# sensor_board.net
KiCad netlist of a schematic drawn in EAGLE
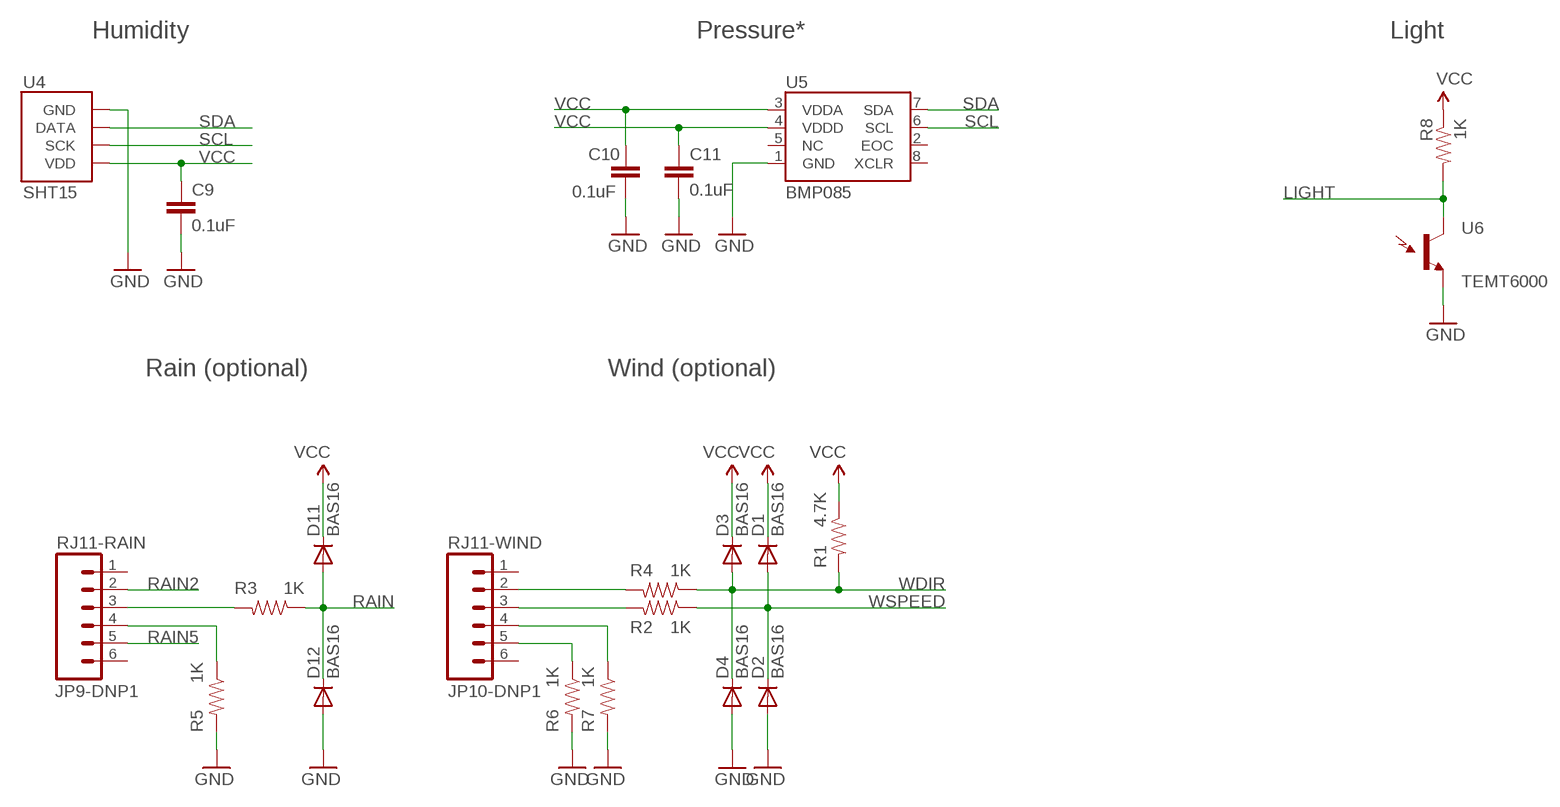
[diagram p0: schematic, sheet 1]

(export (version "E")
  (design (tool "Eeschema 10.0.6"))
  (components
    (comp (ref "C9")
      (value "0.1uF")
      (footprint "eagle-import:0402-CAP")
      (libsource (lib "eagle-import") (part "CAP0402-CAP"))
    )
    (comp (ref "C10")
      (value "0.1uF")
      (footprint "eagle-import:0402-CAP")
      (libsource (lib "eagle-import") (part "CAP0402-CAP"))
    )
    (comp (ref "C11")
      (value "0.1uF")
      (footprint "eagle-import:0402-CAP")
      (libsource (lib "eagle-import") (part "CAP0402-CAP"))
    )
    (comp (ref "D1")
      (value "BAS16")
      (footprint "eagle-import:SOD-323")
      (libsource (lib "eagle-import") (part "DIODESOD"))
    )
    (comp (ref "D2")
      (value "BAS16")
      (footprint "eagle-import:SOD-323")
      (libsource (lib "eagle-import") (part "DIODESOD"))
    )
    (comp (ref "D3")
      (value "BAS16")
      (footprint "eagle-import:SOD-323")
      (libsource (lib "eagle-import") (part "DIODESOD"))
    )
    (comp (ref "D4")
      (value "BAS16")
      (footprint "eagle-import:SOD-323")
      (libsource (lib "eagle-import") (part "DIODESOD"))
    )
    (comp (ref "D11")
      (value "BAS16")
      (footprint "eagle-import:SOD-323")
      (libsource (lib "eagle-import") (part "DIODESOD"))
    )
    (comp (ref "D12")
      (value "BAS16")
      (footprint "eagle-import:SOD-323")
      (libsource (lib "eagle-import") (part "DIODESOD"))
    )
    (comp (ref "JP9-DNP1")
      (value "RJ11-RAIN")
      (footprint "eagle-import:RJ11-6")
      (libsource (lib "eagle-import") (part "RJ11-6PTH"))
    )
    (comp (ref "JP10-DNP1")
      (value "RJ11-WIND")
      (footprint "eagle-import:RJ11-6")
      (libsource (lib "eagle-import") (part "RJ11-6PTH"))
    )
    (comp (ref "R1")
      (value "4.7K")
      (footprint "eagle-import:0402-RES")
      (libsource (lib "eagle-import") (part "RESISTOR0402-RES"))
    )
    (comp (ref "R2")
      (value "1K")
      (footprint "eagle-import:0402-RES")
      (libsource (lib "eagle-import") (part "RESISTOR0402-RES"))
    )
    (comp (ref "R3")
      (value "1K")
      (footprint "eagle-import:0402-RES")
      (libsource (lib "eagle-import") (part "RESISTOR0402-RES"))
    )
    (comp (ref "R4")
      (value "1K")
      (footprint "eagle-import:0402-RES")
      (libsource (lib "eagle-import") (part "RESISTOR0402-RES"))
    )
    (comp (ref "R5")
      (value "1K")
      (footprint "eagle-import:0402-RES")
      (libsource (lib "eagle-import") (part "RESISTOR0402-RES"))
    )
    (comp (ref "R6")
      (value "1K")
      (footprint "eagle-import:0402-RES")
      (libsource (lib "eagle-import") (part "RESISTOR0402-RES"))
    )
    (comp (ref "R7")
      (value "1K")
      (footprint "eagle-import:0402-RES")
      (libsource (lib "eagle-import") (part "RESISTOR0402-RES"))
    )
    (comp (ref "R8")
      (value "1K")
      (footprint "eagle-import:0402-RES")
      (libsource (lib "eagle-import") (part "RESISTOR0402-RES"))
    )
    (comp (ref "U4")
      (value "SHT15")
      (footprint "eagle-import:SHT1X")
      (libsource (lib "eagle-import") (part "SHT1XSMD"))
    )
    (comp (ref "U5")
      (value "BMP085")
      (footprint "eagle-import:BMP085")
      (libsource (lib "eagle-import") (part "BMP085"))
    )
    (comp (ref "U6")
      (value "TEMT6000")
      (footprint "eagle-import:TEMT6000-SEN")
      (libsource (lib "eagle-import") (part "TEMT6000"))
    )
  )
  (nets
    (net (code "1") (name "/LIGHT") (class "Default")
      (node (ref "R8") (pin "2") (pinfunction "2_2") (pintype "passive"))
      (node (ref "U6") (pin "COLLECTOR") (pinfunction "C1_COLLECTOR") (pintype "passive"))
    )
    (net (code "2") (name "/RAIN") (class "Default")
      (node (ref "D11") (pin "2") (pinfunction "A_2") (pintype "passive"))
      (node (ref "D12") (pin "1") (pinfunction "C_1") (pintype "passive"))
      (node (ref "R3") (pin "1") (pinfunction "1_1") (pintype "passive"))
    )
    (net (code "3") (name "/RAIN2") (class "Default")
      (node (ref "JP9-DNP1") (pin "2") (pinfunction "2_2") (pintype "passive"))
    )
    (net (code "4") (name "/RAIN5") (class "Default")
      (node (ref "JP9-DNP1") (pin "5") (pinfunction "5_5") (pintype "passive"))
    )
    (net (code "5") (name "/SCL") (class "Default")
      (node (ref "U4") (pin "3") (pinfunction "SCK_3") (pintype "input"))
      (node (ref "U5") (pin "6") (pinfunction "SCL_6") (pintype "input"))
    )
    (net (code "6") (name "/SDA") (class "Default")
      (node (ref "U4") (pin "2") (pinfunction "DATA_2") (pintype "bidirectional"))
      (node (ref "U5") (pin "7") (pinfunction "SDA_7") (pintype "bidirectional"))
    )
    (net (code "7") (name "/WDIR") (class "Default")
      (node (ref "D3") (pin "2") (pinfunction "A_2") (pintype "passive"))
      (node (ref "D4") (pin "1") (pinfunction "C_1") (pintype "passive"))
      (node (ref "R1") (pin "2") (pinfunction "2_2") (pintype "passive"))
      (node (ref "R4") (pin "1") (pinfunction "1_1") (pintype "passive"))
    )
    (net (code "8") (name "/WSPEED") (class "Default")
      (node (ref "D1") (pin "2") (pinfunction "A_2") (pintype "passive"))
      (node (ref "D2") (pin "1") (pinfunction "C_1") (pintype "passive"))
      (node (ref "R2") (pin "1") (pinfunction "1_1") (pintype "passive"))
    )
    (net (code "9") (name "GND") (class "Default")
      (node (ref "C10") (pin "1") (pinfunction "1_1") (pintype "passive"))
      (node (ref "C11") (pin "2") (pinfunction "2_2") (pintype "passive"))
      (node (ref "C9") (pin "2") (pinfunction "2_2") (pintype "passive"))
      (node (ref "D12") (pin "2") (pinfunction "A_2") (pintype "passive"))
      (node (ref "D2") (pin "2") (pinfunction "A_2") (pintype "passive"))
      (node (ref "D4") (pin "2") (pinfunction "A_2") (pintype "passive"))
      (node (ref "R5") (pin "2") (pinfunction "2_2") (pintype "passive"))
      (node (ref "R6") (pin "2") (pinfunction "2_2") (pintype "passive"))
      (node (ref "R7") (pin "2") (pinfunction "2_2") (pintype "passive"))
      (node (ref "U4") (pin "1") (pinfunction "GND_1") (pintype "power_in"))
      (node (ref "U5") (pin "1") (pinfunction "GND_1") (pintype "power_in"))
      (node (ref "U6") (pin "EMITTER") (pinfunction "E1_EMITTER") (pintype "passive"))
    )
    (net (code "10") (name "Net-(JP9-DNP1-Pad3)") (class "Default")
      (node (ref "JP9-DNP1") (pin "3") (pinfunction "3_3") (pintype "passive"))
      (node (ref "R3") (pin "2") (pinfunction "2_2") (pintype "passive"))
    )
    (net (code "11") (name "Net-(JP9-DNP1-Pad4)") (class "Default")
      (node (ref "JP9-DNP1") (pin "4") (pinfunction "4_4") (pintype "passive"))
      (node (ref "R5") (pin "1") (pinfunction "1_1") (pintype "passive"))
    )
    (net (code "12") (name "Net-(JP10-DNP1-Pad2)") (class "Default")
      (node (ref "JP10-DNP1") (pin "2") (pinfunction "2_2") (pintype "passive"))
      (node (ref "R4") (pin "2") (pinfunction "2_2") (pintype "passive"))
    )
    (net (code "13") (name "Net-(JP10-DNP1-Pad3)") (class "Default")
      (node (ref "JP10-DNP1") (pin "3") (pinfunction "3_3") (pintype "passive"))
      (node (ref "R2") (pin "2") (pinfunction "2_2") (pintype "passive"))
    )
    (net (code "14") (name "Net-(JP10-DNP1-Pad4)") (class "Default")
      (node (ref "JP10-DNP1") (pin "4") (pinfunction "4_4") (pintype "passive"))
      (node (ref "R7") (pin "1") (pinfunction "1_1") (pintype "passive"))
    )
    (net (code "15") (name "Net-(JP10-DNP1-Pad5)") (class "Default")
      (node (ref "JP10-DNP1") (pin "5") (pinfunction "5_5") (pintype "passive"))
      (node (ref "R6") (pin "1") (pinfunction "1_1") (pintype "passive"))
    )
    (net (code "16") (name "VCC") (class "Default")
      (node (ref "C10") (pin "2") (pinfunction "2_2") (pintype "passive"))
      (node (ref "C11") (pin "1") (pinfunction "1_1") (pintype "passive"))
      (node (ref "C9") (pin "1") (pinfunction "1_1") (pintype "passive"))
      (node (ref "D1") (pin "1") (pinfunction "C_1") (pintype "passive"))
      (node (ref "D11") (pin "1") (pinfunction "C_1") (pintype "passive"))
      (node (ref "D3") (pin "1") (pinfunction "C_1") (pintype "passive"))
      (node (ref "R1") (pin "1") (pinfunction "1_1") (pintype "passive"))
      (node (ref "R8") (pin "1") (pinfunction "1_1") (pintype "passive"))
      (node (ref "U4") (pin "4") (pinfunction "VDD_4") (pintype "power_in"))
      (node (ref "U5") (pin "3") (pinfunction "VDDA_3") (pintype "power_in"))
      (node (ref "U5") (pin "4") (pinfunction "VDDD_4") (pintype "power_in"))
    )
    (net (code "17") (name "unconnected-(JP9-DNP1-Pad1)") (class "Default")
      (node (ref "JP9-DNP1") (pin "1") (pinfunction "1_1") (pintype "passive"))
    )
    (net (code "18") (name "unconnected-(JP9-DNP1-Pad6)") (class "Default")
      (node (ref "JP9-DNP1") (pin "6") (pinfunction "6_6") (pintype "passive"))
    )
    (net (code "19") (name "unconnected-(JP10-DNP1-Pad1)") (class "Default")
      (node (ref "JP10-DNP1") (pin "1") (pinfunction "1_1") (pintype "passive"))
    )
    (net (code "20") (name "unconnected-(JP10-DNP1-Pad6)") (class "Default")
      (node (ref "JP10-DNP1") (pin "6") (pinfunction "6_6") (pintype "passive"))
    )
    (net (code "21") (name "unconnected-(U5-EOC-Pad2)") (class "Default")
      (node (ref "U5") (pin "2") (pinfunction "EOC_2") (pintype "output"))
    )
    (net (code "22") (name "unconnected-(U5-NC-Pad5)") (class "Default")
      (node (ref "U5") (pin "5") (pinfunction "NC_5") (pintype "bidirectional"))
    )
    (net (code "23") (name "unconnected-(U5-XCLR-Pad8)") (class "Default")
      (node (ref "U5") (pin "8") (pinfunction "XCLR_8") (pintype "input"))
    )
  )
)
